# sense_pcb_b.net
KiCad netlist of a schematic drawn in EAGLE
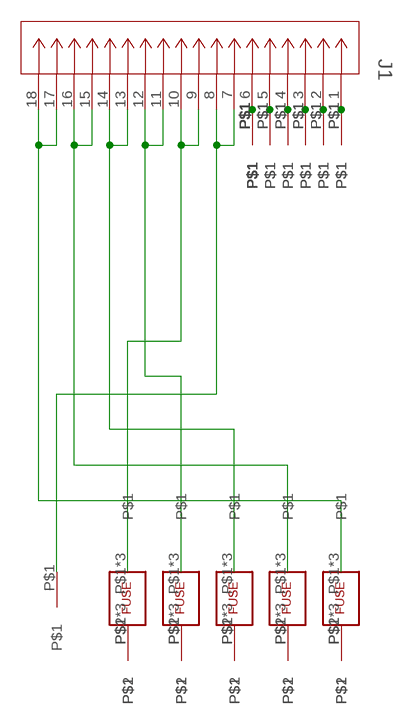
[diagram p0: schematic, sheet 1]

(export (version "E")
  (design (tool "Eeschema 10.0.6"))
  (components
    (comp (ref "J1")
      (value "DF11-18DP-2DSA(24)")
      (footprint "eagle-import:CON18_2X9_UF_DF11_HIR")
      (fields (field (name "COPYRIGHT") "Copyright (C) 2023 Ultra Librarian. All rights reserved."))
      (libsource (lib "eagle-import") (part "DF11-18DP-2DSA(24)"))
    )
    (comp (ref "U$1")
      (value "FUSE")
      (footprint "eagle-import:FUSE_PADS")
      (libsource (lib "eagle-import") (part "FUSE"))
    )
    (comp (ref "U$2")
      (value "FUSE")
      (footprint "eagle-import:FUSE_PADS")
      (libsource (lib "eagle-import") (part "FUSE"))
    )
    (comp (ref "U$3")
      (value "FUSE")
      (footprint "eagle-import:FUSE_PADS")
      (libsource (lib "eagle-import") (part "FUSE"))
    )
    (comp (ref "U$4")
      (value "FUSE")
      (footprint "eagle-import:FUSE_PADS")
      (libsource (lib "eagle-import") (part "FUSE"))
    )
    (comp (ref "U$5")
      (value "FUSE")
      (footprint "eagle-import:FUSE_PADS")
      (libsource (lib "eagle-import") (part "FUSE"))
    )
    (comp (ref "U$6")
      (value "BB_CONTACT")
      (footprint "eagle-import:BB_CONTACT")
      (libsource (lib "eagle-import") (part "BB_CONTACT"))
    )
    (comp (ref "U$7")
      (value "BB_CONTACT")
      (footprint "eagle-import:BB_CONTACT")
      (libsource (lib "eagle-import") (part "BB_CONTACT"))
    )
    (comp (ref "U$8")
      (value "BB_CONTACT")
      (footprint "eagle-import:BB_CONTACT")
      (libsource (lib "eagle-import") (part "BB_CONTACT"))
    )
    (comp (ref "U$9")
      (value "BB_CONTACT")
      (footprint "eagle-import:BB_CONTACT")
      (libsource (lib "eagle-import") (part "BB_CONTACT"))
    )
    (comp (ref "U$10")
      (value "BB_CONTACT")
      (footprint "eagle-import:BB_CONTACT")
      (libsource (lib "eagle-import") (part "BB_CONTACT"))
    )
    (comp (ref "U$11")
      (value "BB_CONTACT")
      (footprint "eagle-import:BB_CONTACT")
      (libsource (lib "eagle-import") (part "BB_CONTACT"))
    )
    (comp (ref "U$12")
      (value "THERM_PIN")
      (footprint "eagle-import:THERM_PIN")
      (libsource (lib "eagle-import") (part "THERM_PIN"))
    )
    (comp (ref "U$13")
      (value "THERM_PIN")
      (footprint "eagle-import:THERM_PIN")
      (libsource (lib "eagle-import") (part "THERM_PIN"))
    )
    (comp (ref "U$14")
      (value "THERM_PIN")
      (footprint "eagle-import:THERM_PIN")
      (libsource (lib "eagle-import") (part "THERM_PIN"))
    )
    (comp (ref "U$15")
      (value "THERM_PIN")
      (footprint "eagle-import:THERM_PIN")
      (libsource (lib "eagle-import") (part "THERM_PIN"))
    )
    (comp (ref "U$16")
      (value "THERM_PIN")
      (footprint "eagle-import:THERM_PIN")
      (libsource (lib "eagle-import") (part "THERM_PIN"))
    )
    (comp (ref "U$17")
      (value "THERM_PIN")
      (footprint "eagle-import:THERM_PIN")
      (libsource (lib "eagle-import") (part "THERM_PIN"))
    )
    (comp (ref "U$18")
      (value "THERM_PIN")
      (footprint "eagle-import:THERM_PIN")
      (libsource (lib "eagle-import") (part "THERM_PIN"))
    )
    (comp (ref "U$19")
      (value "THERM_PIN")
      (footprint "eagle-import:THERM_PIN")
      (libsource (lib "eagle-import") (part "THERM_PIN"))
    )
    (comp (ref "U$20")
      (value "THERM_PIN")
      (footprint "eagle-import:THERM_PIN")
      (libsource (lib "eagle-import") (part "THERM_PIN"))
    )
    (comp (ref "U$21")
      (value "THERM_PIN")
      (footprint "eagle-import:THERM_PIN")
      (libsource (lib "eagle-import") (part "THERM_PIN"))
    )
    (comp (ref "U$22")
      (value "THERM_PIN")
      (footprint "eagle-import:THERM_PIN")
      (libsource (lib "eagle-import") (part "THERM_PIN"))
    )
    (comp (ref "U$23")
      (value "THERM_PIN")
      (footprint "eagle-import:THERM_PIN")
      (libsource (lib "eagle-import") (part "THERM_PIN"))
    )
    (comp (ref "U$24")
      (value "THERM_PIN")
      (footprint "eagle-import:THERM_PIN")
      (libsource (lib "eagle-import") (part "THERM_PIN"))
    )
    (comp (ref "U$25")
      (value "THERM_PIN")
      (footprint "eagle-import:THERM_PIN")
      (libsource (lib "eagle-import") (part "THERM_PIN"))
    )
    (comp (ref "U$26")
      (value "THERM_PIN")
      (footprint "eagle-import:THERM_PIN")
      (libsource (lib "eagle-import") (part "THERM_PIN"))
    )
    (comp (ref "U$27")
      (value "THERM_PIN")
      (footprint "eagle-import:THERM_PIN")
      (libsource (lib "eagle-import") (part "THERM_PIN"))
    )
    (comp (ref "U$28")
      (value "THERM_PIN")
      (footprint "eagle-import:THERM_PIN")
      (libsource (lib "eagle-import") (part "THERM_PIN"))
    )
    (comp (ref "U$29")
      (value "THERM_PIN")
      (footprint "eagle-import:THERM_PIN")
      (libsource (lib "eagle-import") (part "THERM_PIN"))
    )
    (comp (ref "U$30")
      (value "THERM_PIN")
      (footprint "eagle-import:THERM_PIN")
      (libsource (lib "eagle-import") (part "THERM_PIN"))
    )
    (comp (ref "U$31")
      (value "THERM_PIN")
      (footprint "eagle-import:THERM_PIN")
      (libsource (lib "eagle-import") (part "THERM_PIN"))
    )
  )
  (nets
    (net (code "1") (name "Net-(J1-Pad1)") (class "Default")
      (node (ref "J1") (pin "1") (pinfunction "1_1") (pintype "passive"))
      (node (ref "U$30") (pin "P$1") (pinfunction "P$1_P$1") (pintype "bidirectional"))
      (node (ref "U$31") (pin "P$1") (pinfunction "P$1_P$1") (pintype "bidirectional"))
    )
    (net (code "2") (name "Net-(J1-Pad2)") (class "Default")
      (node (ref "J1") (pin "2") (pinfunction "2_2") (pintype "passive"))
      (node (ref "U$28") (pin "P$1") (pinfunction "P$1_P$1") (pintype "bidirectional"))
      (node (ref "U$29") (pin "P$1") (pinfunction "P$1_P$1") (pintype "bidirectional"))
    )
    (net (code "3") (name "Net-(J1-Pad3)") (class "Default")
      (node (ref "J1") (pin "3") (pinfunction "3_3") (pintype "passive"))
      (node (ref "U$26") (pin "P$1") (pinfunction "P$1_P$1") (pintype "bidirectional"))
      (node (ref "U$27") (pin "P$1") (pinfunction "P$1_P$1") (pintype "bidirectional"))
    )
    (net (code "4") (name "Net-(J1-Pad4)") (class "Default")
      (node (ref "J1") (pin "4") (pinfunction "4_4") (pintype "passive"))
      (node (ref "U$24") (pin "P$1") (pinfunction "P$1_P$1") (pintype "bidirectional"))
      (node (ref "U$25") (pin "P$1") (pinfunction "P$1_P$1") (pintype "bidirectional"))
    )
    (net (code "5") (name "Net-(J1-Pad5)") (class "Default")
      (node (ref "J1") (pin "5") (pinfunction "5_5") (pintype "passive"))
      (node (ref "U$22") (pin "P$1") (pinfunction "P$1_P$1") (pintype "bidirectional"))
      (node (ref "U$23") (pin "P$1") (pinfunction "P$1_P$1") (pintype "bidirectional"))
    )
    (net (code "6") (name "Net-(J1-Pad6)") (class "Default")
      (node (ref "J1") (pin "6") (pinfunction "6_6") (pintype "passive"))
      (node (ref "U$12") (pin "P$1") (pinfunction "P$1_P$1") (pintype "bidirectional"))
      (node (ref "U$13") (pin "P$1") (pinfunction "P$1_P$1") (pintype "bidirectional"))
      (node (ref "U$14") (pin "P$1") (pinfunction "P$1_P$1") (pintype "bidirectional"))
      (node (ref "U$15") (pin "P$1") (pinfunction "P$1_P$1") (pintype "bidirectional"))
      (node (ref "U$16") (pin "P$1") (pinfunction "P$1_P$1") (pintype "bidirectional"))
      (node (ref "U$17") (pin "P$1") (pinfunction "P$1_P$1") (pintype "bidirectional"))
      (node (ref "U$18") (pin "P$1") (pinfunction "P$1_P$1") (pintype "bidirectional"))
      (node (ref "U$19") (pin "P$1") (pinfunction "P$1_P$1") (pintype "bidirectional"))
      (node (ref "U$20") (pin "P$1") (pinfunction "P$1_P$1") (pintype "bidirectional"))
      (node (ref "U$21") (pin "P$1") (pinfunction "P$1_P$1") (pintype "bidirectional"))
    )
    (net (code "7") (name "Net-(J1-Pad7)") (class "Default")
      (node (ref "J1") (pin "7") (pinfunction "7_7") (pintype "passive"))
      (node (ref "J1") (pin "8") (pinfunction "8_8") (pintype "passive"))
      (node (ref "U$11") (pin "P$1") (pinfunction "P$1_P$1") (pintype "bidirectional"))
    )
    (net (code "8") (name "Net-(J1-Pad10)") (class "Default")
      (node (ref "J1") (pin "10") (pinfunction "10_10") (pintype "passive"))
      (node (ref "J1") (pin "9") (pinfunction "9_9") (pintype "passive"))
      (node (ref "U$1") (pin "P$1") (pinfunction "P$1_P$1") (pintype "bidirectional"))
      (node (ref "U$1") (pin "P$3") (pinfunction "P$1_P$3") (pintype "bidirectional"))
      (node (ref "U$1") (pin "P$5") (pinfunction "P$1_P$5") (pintype "bidirectional"))
    )
    (net (code "9") (name "Net-(J1-Pad11)") (class "Default")
      (node (ref "J1") (pin "11") (pinfunction "11_11") (pintype "passive"))
      (node (ref "J1") (pin "12") (pinfunction "12_12") (pintype "passive"))
      (node (ref "U$2") (pin "P$1") (pinfunction "P$1_P$1") (pintype "bidirectional"))
      (node (ref "U$2") (pin "P$3") (pinfunction "P$1_P$3") (pintype "bidirectional"))
      (node (ref "U$2") (pin "P$5") (pinfunction "P$1_P$5") (pintype "bidirectional"))
    )
    (net (code "10") (name "Net-(J1-Pad13)") (class "Default")
      (node (ref "J1") (pin "13") (pinfunction "13_13") (pintype "passive"))
      (node (ref "J1") (pin "14") (pinfunction "14_14") (pintype "passive"))
      (node (ref "U$3") (pin "P$1") (pinfunction "P$1_P$1") (pintype "bidirectional"))
      (node (ref "U$3") (pin "P$3") (pinfunction "P$1_P$3") (pintype "bidirectional"))
      (node (ref "U$3") (pin "P$5") (pinfunction "P$1_P$5") (pintype "bidirectional"))
    )
    (net (code "11") (name "Net-(J1-Pad15)") (class "Default")
      (node (ref "J1") (pin "15") (pinfunction "15_15") (pintype "passive"))
      (node (ref "J1") (pin "16") (pinfunction "16_16") (pintype "passive"))
      (node (ref "U$4") (pin "P$1") (pinfunction "P$1_P$1") (pintype "bidirectional"))
      (node (ref "U$4") (pin "P$3") (pinfunction "P$1_P$3") (pintype "bidirectional"))
      (node (ref "U$4") (pin "P$5") (pinfunction "P$1_P$5") (pintype "bidirectional"))
    )
    (net (code "12") (name "Net-(J1-Pad17)") (class "Default")
      (node (ref "J1") (pin "17") (pinfunction "17_17") (pintype "passive"))
      (node (ref "J1") (pin "18") (pinfunction "18_18") (pintype "passive"))
      (node (ref "U$5") (pin "P$1") (pinfunction "P$1_P$1") (pintype "bidirectional"))
      (node (ref "U$5") (pin "P$3") (pinfunction "P$1_P$3") (pintype "bidirectional"))
      (node (ref "U$5") (pin "P$5") (pinfunction "P$1_P$5") (pintype "bidirectional"))
    )
    (net (code "13") (name "Net-(U$1-P$2-PadP$4)") (class "Default")
      (node (ref "U$1") (pin "P$2") (pinfunction "P$2_P$2") (pintype "bidirectional"))
      (node (ref "U$1") (pin "P$4") (pinfunction "P$2_P$4") (pintype "bidirectional"))
      (node (ref "U$1") (pin "P$6") (pinfunction "P$2_P$6") (pintype "bidirectional"))
      (node (ref "U$6") (pin "P$1") (pinfunction "P$1_P$1") (pintype "bidirectional"))
    )
    (net (code "14") (name "Net-(U$2-P$2-PadP$4)") (class "Default")
      (node (ref "U$2") (pin "P$2") (pinfunction "P$2_P$2") (pintype "bidirectional"))
      (node (ref "U$2") (pin "P$4") (pinfunction "P$2_P$4") (pintype "bidirectional"))
      (node (ref "U$2") (pin "P$6") (pinfunction "P$2_P$6") (pintype "bidirectional"))
      (node (ref "U$7") (pin "P$1") (pinfunction "P$1_P$1") (pintype "bidirectional"))
    )
    (net (code "15") (name "Net-(U$3-P$2-PadP$4)") (class "Default")
      (node (ref "U$3") (pin "P$2") (pinfunction "P$2_P$2") (pintype "bidirectional"))
      (node (ref "U$3") (pin "P$4") (pinfunction "P$2_P$4") (pintype "bidirectional"))
      (node (ref "U$3") (pin "P$6") (pinfunction "P$2_P$6") (pintype "bidirectional"))
      (node (ref "U$8") (pin "P$1") (pinfunction "P$1_P$1") (pintype "bidirectional"))
    )
    (net (code "16") (name "Net-(U$4-P$2-PadP$4)") (class "Default")
      (node (ref "U$4") (pin "P$2") (pinfunction "P$2_P$2") (pintype "bidirectional"))
      (node (ref "U$4") (pin "P$4") (pinfunction "P$2_P$4") (pintype "bidirectional"))
      (node (ref "U$4") (pin "P$6") (pinfunction "P$2_P$6") (pintype "bidirectional"))
      (node (ref "U$9") (pin "P$1") (pinfunction "P$1_P$1") (pintype "bidirectional"))
    )
    (net (code "17") (name "Net-(U$10-PadP$1)") (class "Default")
      (node (ref "U$10") (pin "P$1") (pinfunction "P$1_P$1") (pintype "bidirectional"))
      (node (ref "U$5") (pin "P$2") (pinfunction "P$2_P$2") (pintype "bidirectional"))
      (node (ref "U$5") (pin "P$4") (pinfunction "P$2_P$4") (pintype "bidirectional"))
      (node (ref "U$5") (pin "P$6") (pinfunction "P$2_P$6") (pintype "bidirectional"))
    )
  )
)
